# esp8266_schematic.net
KiCad netlist of a schematic drawn in EAGLE
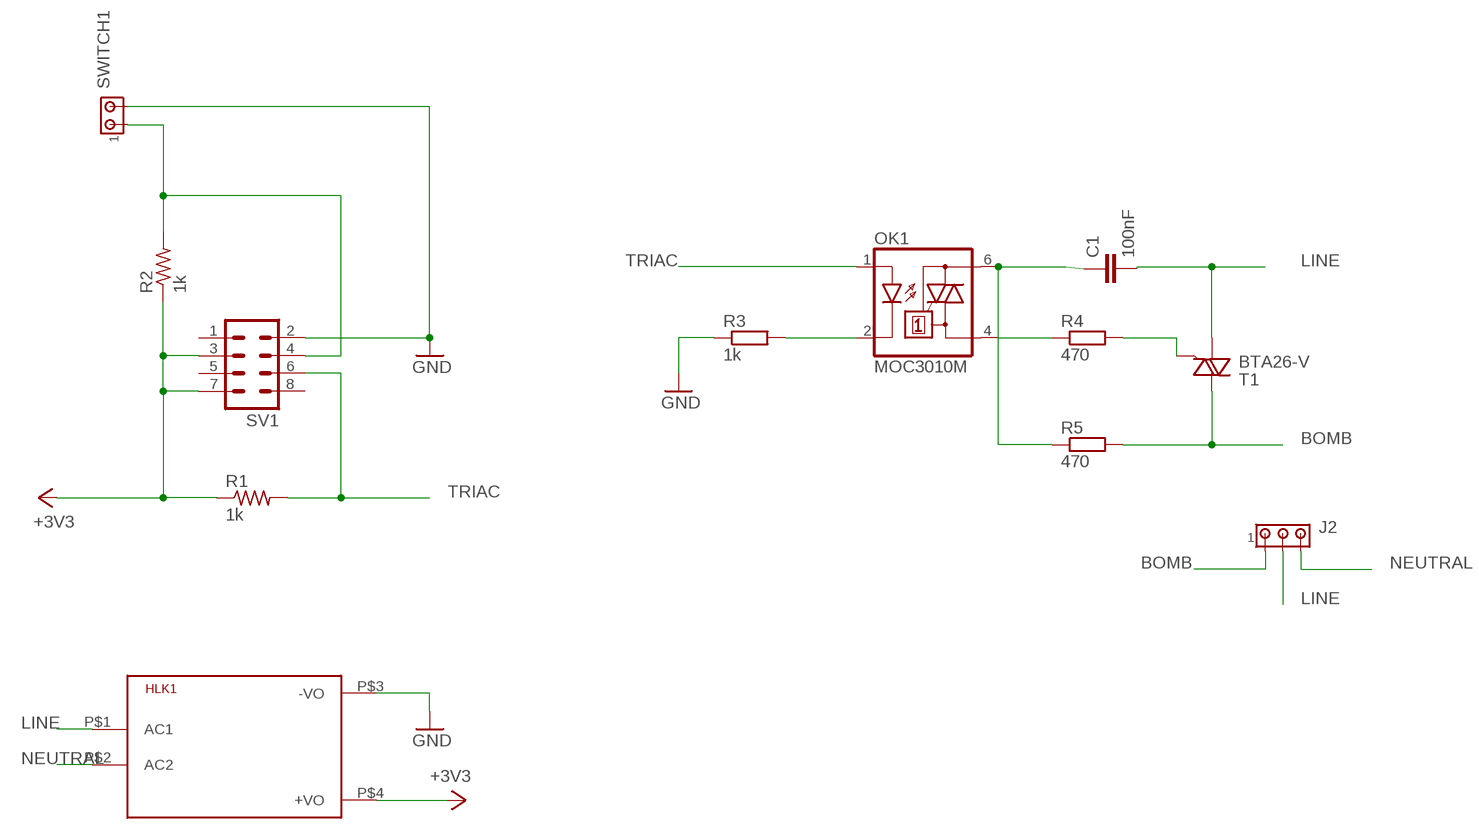
[diagram p0: schematic, sheet 1]

(export (version "E")
  (design (tool "Eeschema 10.0.6"))
  (components
    (comp (ref "C1")
      (value "100nF")
      (footprint "eagle-import:C102-043X133")
      (libsource (lib "eagle-import") (part "C-EU102-043X133"))
    )
    (comp (ref "HLK1")
      (value "HLK-PM013W")
      (footprint "eagle-import:HLK-PM01")
      (libsource (lib "eagle-import") (part "HLK-PM013W"))
    )
    (comp (ref "J2")
      (value "MTA03-100")
      (footprint "eagle-import:10X03MTA")
      (libsource (lib "eagle-import") (part "MTA03-100"))
    )
    (comp (ref "OK1")
      (value "MOC3010M")
      (footprint "eagle-import:DIL06")
      (fields (field (name "MF") "FAIRCHILD SEMICONDUCTOR") (field (name "MPN") "MOC3010-M"))
      (libsource (lib "eagle-import") (part "MOC30M10"))
    )
    (comp (ref "R1")
      (value "1k")
      (footprint "eagle-import:0207_2V")
      (libsource (lib "eagle-import") (part "R-US_0207/2V"))
    )
    (comp (ref "R2")
      (value "1k")
      (footprint "eagle-import:0207_2V")
      (libsource (lib "eagle-import") (part "R-US_0207/2V"))
    )
    (comp (ref "R3")
      (value "1k")
      (footprint "eagle-import:0204_5")
      (libsource (lib "eagle-import") (part "R-EU_0204/5"))
    )
    (comp (ref "R4")
      (value "470")
      (footprint "eagle-import:0207_15")
      (libsource (lib "eagle-import") (part "R-EU_0207/15"))
    )
    (comp (ref "R5")
      (value "470")
      (footprint "eagle-import:0207_15")
      (libsource (lib "eagle-import") (part "R-EU_0207/15"))
    )
    (comp (ref "SV1")
      (value "MA04-2")
      (footprint "eagle-import:MA04-2")
      (libsource (lib "eagle-import") (part "MA04-2"))
    )
    (comp (ref "SWITCH1")
      (value "MTA02-100")
      (footprint "eagle-import:10X02MTA")
      (libsource (lib "eagle-import") (part "MTA02-100"))
    )
    (comp (ref "T1")
      (value "BTA26-V")
      (footprint "eagle-import:TOP3S-1")
      (libsource (lib "eagle-import") (part "BTA26-V"))
    )
  )
  (nets
    (net (code "1") (name "+3V3") (class "Default")
      (node (ref "HLK1") (pin "P$4") (pinfunction "+VO_P$4") (pintype "bidirectional"))
      (node (ref "R1") (pin "1") (pinfunction "1_1") (pintype "passive"))
      (node (ref "R2") (pin "1") (pinfunction "1_1") (pintype "passive"))
      (node (ref "SV1") (pin "3") (pinfunction "3_3") (pintype "passive"))
      (node (ref "SV1") (pin "7") (pinfunction "7_7") (pintype "passive"))
    )
    (net (code "2") (name "/BOMB") (class "Default")
      (node (ref "J2") (pin "1") (pinfunction "1_1") (pintype "passive"))
      (node (ref "R5") (pin "2") (pinfunction "2_2") (pintype "passive"))
      (node (ref "T1") (pin "A2") (pinfunction "A2_A2") (pintype "passive"))
    )
    (net (code "3") (name "/LINE") (class "Default")
      (node (ref "C1") (pin "2") (pinfunction "2_2") (pintype "passive"))
      (node (ref "HLK1") (pin "P$1") (pinfunction "AC1_P$1") (pintype "bidirectional"))
      (node (ref "J2") (pin "2") (pinfunction "2_2") (pintype "passive"))
      (node (ref "T1") (pin "A1") (pinfunction "A1_A1") (pintype "passive"))
    )
    (net (code "4") (name "/NEUTRAL") (class "Default")
      (node (ref "HLK1") (pin "P$2") (pinfunction "AC2_P$2") (pintype "bidirectional"))
      (node (ref "J2") (pin "3") (pinfunction "3_3") (pintype "passive"))
    )
    (net (code "5") (name "/TRIAC") (class "Default")
      (node (ref "OK1") (pin "1") (pinfunction "A_1") (pintype "passive"))
      (node (ref "R1") (pin "2") (pinfunction "2_2") (pintype "passive"))
      (node (ref "SV1") (pin "6") (pinfunction "6_6") (pintype "passive"))
    )
    (net (code "6") (name "GND") (class "Default")
      (node (ref "HLK1") (pin "P$3") (pinfunction "-VO_P$3") (pintype "bidirectional"))
      (node (ref "R3") (pin "1") (pinfunction "1_1") (pintype "passive"))
      (node (ref "SV1") (pin "2") (pinfunction "2_2") (pintype "passive"))
      (node (ref "SWITCH1") (pin "2") (pinfunction "2_2") (pintype "passive"))
    )
    (net (code "7") (name "Net-(OK1-A1)") (class "Default")
      (node (ref "OK1") (pin "4") (pinfunction "A1_4") (pintype "passive"))
      (node (ref "R4") (pin "1") (pinfunction "1_1") (pintype "passive"))
    )
    (net (code "8") (name "Net-(OK1-A2)") (class "Default")
      (node (ref "C1") (pin "1") (pinfunction "1_1") (pintype "passive"))
      (node (ref "OK1") (pin "6") (pinfunction "A2_6") (pintype "passive"))
      (node (ref "R5") (pin "1") (pinfunction "1_1") (pintype "passive"))
    )
    (net (code "9") (name "Net-(OK1-C)") (class "Default")
      (node (ref "OK1") (pin "2") (pinfunction "C_2") (pintype "passive"))
      (node (ref "R3") (pin "2") (pinfunction "2_2") (pintype "passive"))
    )
    (net (code "10") (name "Net-(R2-Pad2)") (class "Default")
      (node (ref "R2") (pin "2") (pinfunction "2_2") (pintype "passive"))
      (node (ref "SV1") (pin "4") (pinfunction "4_4") (pintype "passive"))
      (node (ref "SWITCH1") (pin "1") (pinfunction "1_1") (pintype "passive"))
    )
    (net (code "11") (name "Net-(R4-Pad2)") (class "Default")
      (node (ref "R4") (pin "2") (pinfunction "2_2") (pintype "passive"))
      (node (ref "T1") (pin "G") (pinfunction "G_G") (pintype "passive"))
    )
    (net (code "12") (name "unconnected-(SV1-Pad1)") (class "Default")
      (node (ref "SV1") (pin "1") (pinfunction "1_1") (pintype "passive"))
    )
    (net (code "13") (name "unconnected-(SV1-Pad5)") (class "Default")
      (node (ref "SV1") (pin "5") (pinfunction "5_5") (pintype "passive"))
    )
    (net (code "14") (name "unconnected-(SV1-Pad8)") (class "Default")
      (node (ref "SV1") (pin "8") (pinfunction "8_8") (pintype "passive"))
    )
  )
)
